# Sheet1.net
KiCad netlist of a schematic drawn in Altium Designer
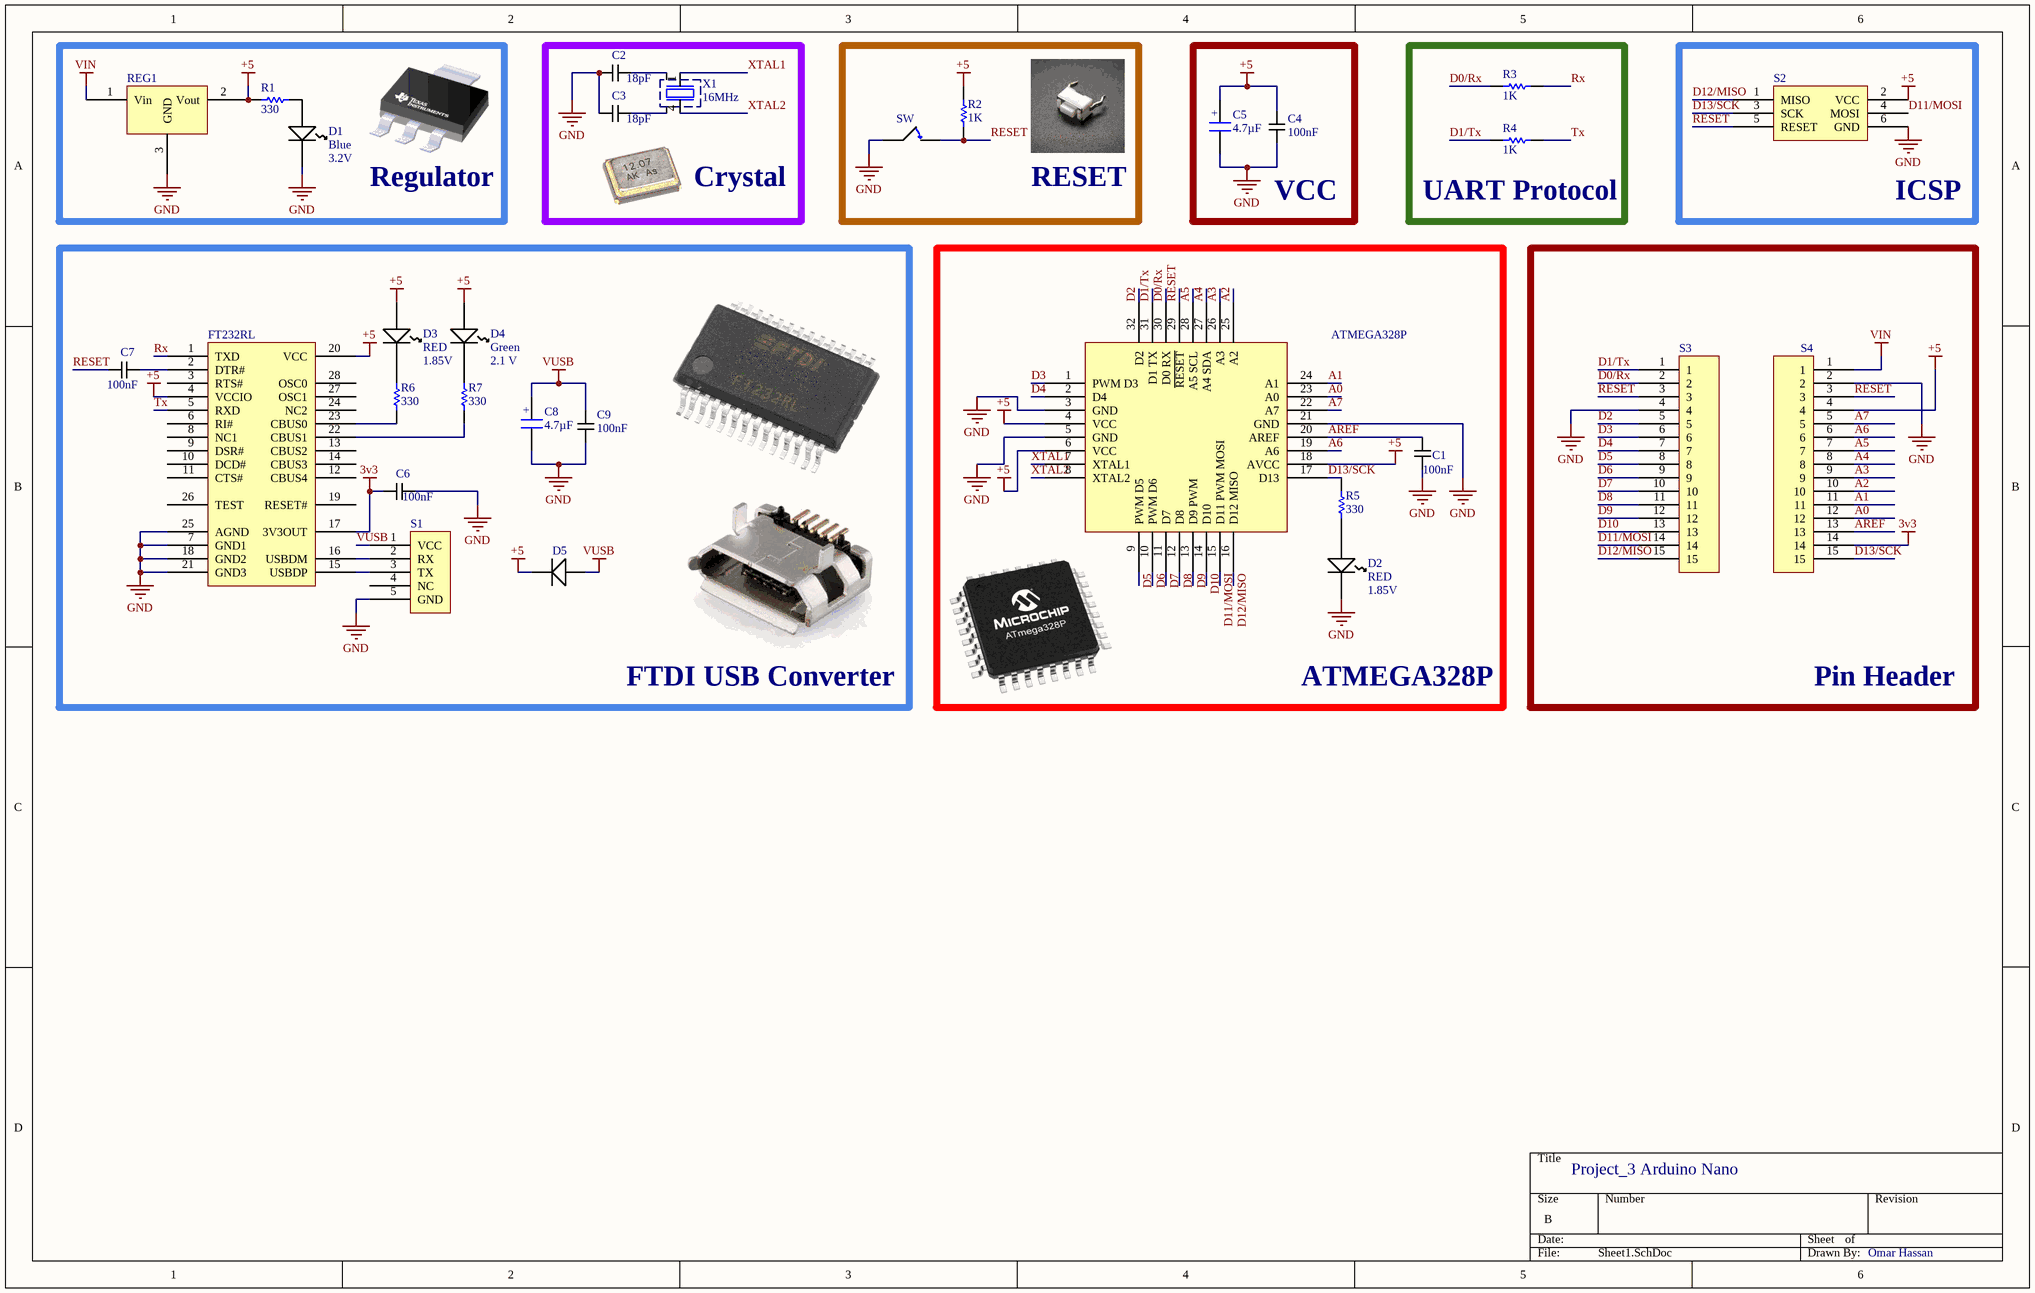
[diagram p0: Sheet1.SchDoc]

(export (version "E")
  (design (tool "Eeschema 10.0.6"))
  (components
    (comp (ref "ATMEGA328P")
      (value "ATMEGA328P-AU")
      (footprint "TQFP80P900X900X120-32N")
      (description "ATMEGA328P-AU, 8 bit AVR Microcontroller 20MHz 1 kB, 32 kB Flash, 2 kB RAM, I2C 32-Pin TQFP")
      (fields (field (name "CREATED BY") "Ritesh Kanjee"))
      (libsource (lib "Atmel Microcontrollers") (part "ATMEGA328P-AU"))
    )
    (comp (ref "C1")
      (value "100nF Ceramic Multilayer Capacitor_1")
      (footprint "CAPCP2012X09N")
      (description "AVX 0805 Standard 100nF Ceramic Multilayer Capacitor, 50 V dc X7R Dielectric ±10% SMD")
      (fields
        (field (name "MANUFACTURER") "AVX")
        (field (name "VOLTAGE") "50V")
        (field (name "CAPACITANCE") "100nF")
        (field (name "CREATOR") "Ritesh Kanjee")
      )
      (libsource (lib "RS Components - Capacitors") (part "100nF Ceramic Multilayer Capacitor_1"))
    )
    (comp (ref "C2")
      (value "C0805C180J5GACTU")
      (footprint "CAPCP2012X09N")
      (description "18pF Ceramic Multilayer Capacitor, 50 V dc C0G Dielectric ±5% SMD")
      (fields
        (field (name "MANUFACTURER") "Kemet")
        (field (name "VOLTAGE") "50V")
        (field (name "CAPACITANCE") "18pF")
        (field (name "CREATOR") "Ritesh Kanjee")
      )
      (libsource (lib "RS Components - Capacitors") (part "18pF Ceramic Multilayer Capacitor, 50 V dc C0G Dielectric ±5% SMD"))
    )
    (comp (ref "C3")
      (value "C0805C180J5GACTU")
      (footprint "CAPCP2012X09N")
      (description "18pF Ceramic Multilayer Capacitor, 50 V dc C0G Dielectric ±5% SMD")
      (fields
        (field (name "MANUFACTURER") "Kemet")
        (field (name "VOLTAGE") "50V")
        (field (name "CAPACITANCE") "18pF")
        (field (name "CREATOR") "Ritesh Kanjee")
      )
      (libsource (lib "RS Components - Capacitors") (part "18pF Ceramic Multilayer Capacitor, 50 V dc C0G Dielectric ±5% SMD"))
    )
    (comp (ref "C4")
      (value "100nF Ceramic Multilayer Capacitor_1")
      (footprint "CAPCP2012X09N")
      (description "AVX 0805 Standard 100nF Ceramic Multilayer Capacitor, 50 V dc X7R Dielectric ±10% SMD")
      (fields
        (field (name "MANUFACTURER") "AVX")
        (field (name "VOLTAGE") "50V")
        (field (name "CAPACITANCE") "100nF")
        (field (name "CREATOR") "Ritesh Kanjee")
      )
      (libsource (lib "RS Components - Capacitors") (part "100nF Ceramic Multilayer Capacitor_1"))
    )
    (comp (ref "C5")
      (value "4.7µF")
      (footprint "CASE A - 3216X18")
      (description "Capacitor,tantalum,SMT,16V,4.7uF,10%,A-case")
      (fields
        (field (name "TOLERANCE") "10%")
        (field (name "VOLTAGE") "16V")
        (field (name "PUBLISHER") "DPSS")
      )
      (libsource (lib "RS Components - Capacitors") (part "4.7µF Tant RS 496-3545"))
    )
    (comp (ref "C6")
      (value "100nF Ceramic Multilayer Capacitor_1")
      (footprint "CAPCP2012X09N")
      (description "AVX 0805 Standard 100nF Ceramic Multilayer Capacitor, 50 V dc X7R Dielectric ±10% SMD")
      (fields
        (field (name "MANUFACTURER") "AVX")
        (field (name "VOLTAGE") "50V")
        (field (name "CAPACITANCE") "100nF")
        (field (name "CREATOR") "Ritesh Kanjee")
      )
      (libsource (lib "RS Components - Capacitors") (part "100nF Ceramic Multilayer Capacitor_1"))
    )
    (comp (ref "C7")
      (value "100nF Ceramic Multilayer Capacitor_1")
      (footprint "CAPCP2012X09N")
      (description "AVX 0805 Standard 100nF Ceramic Multilayer Capacitor, 50 V dc X7R Dielectric ±10% SMD")
      (fields
        (field (name "MANUFACTURER") "AVX")
        (field (name "VOLTAGE") "50V")
        (field (name "CAPACITANCE") "100nF")
        (field (name "CREATOR") "Ritesh Kanjee")
      )
      (libsource (lib "RS Components - Capacitors") (part "100nF Ceramic Multilayer Capacitor_1"))
    )
    (comp (ref "C8")
      (value "4.7µF")
      (footprint "CASE A - 3216X18")
      (description "Capacitor,tantalum,SMT,16V,4.7uF,10%,A-case")
      (fields
        (field (name "TOLERANCE") "10%")
        (field (name "VOLTAGE") "16V")
        (field (name "PUBLISHER") "DPSS")
      )
      (libsource (lib "RS Components - Capacitors") (part "4.7µF Tant RS 496-3545"))
    )
    (comp (ref "C9")
      (value "100nF Ceramic Multilayer Capacitor_1")
      (footprint "CAPCP2012X09N")
      (description "AVX 0805 Standard 100nF Ceramic Multilayer Capacitor, 50 V dc X7R Dielectric ±10% SMD")
      (fields
        (field (name "MANUFACTURER") "AVX")
        (field (name "VOLTAGE") "50V")
        (field (name "CAPACITANCE") "100nF")
        (field (name "CREATOR") "Ritesh Kanjee")
      )
      (libsource (lib "RS Components - Capacitors") (part "100nF Ceramic Multilayer Capacitor_1"))
    )
    (comp (ref "D1")
      (value "Kingbright Blue LED, 60 mcd 120 ° 0805")
      (footprint "LED1913X12NBLUE")
      (fields
        (field (name "MANUFACTURER") "KingBright")
        (field (name "MANUFACTURER PART NO.") "KP-2012PBC-A")
        (field (name "COLOR") "Blue")
        (field (name "FORWARD VOLTAGE") "3.2V")
        (field (name "CREATOR") "Ritesh Kanjee")
      )
      (libsource (lib "KingBright LEDs") (part "Kingbright Blue LED, 60 mcd 120 ° 0805"))
    )
    (comp (ref "D2")
      (value "Kingbright Red LED, 100 mcd 120 ° 0805")
      (footprint "LED1913X12NRED")
      (fields
        (field (name "MANUFACTURER") "KingBright")
        (field (name "MANUFACTURER PART NO.") "KP-2012SRC-PRV")
        (field (name "COLOR") "RED")
        (field (name "FORWARD VOLTAGE") "1.85V")
        (field (name "CREATOR") "Ritesh Kanjee")
      )
      (libsource (lib "KingBright LEDs") (part "Kingbright Red LED, 100 mcd 120 ° 0805"))
    )
    (comp (ref "D3")
      (value "Kingbright Red LED, 100 mcd 120 ° 0805")
      (footprint "LED1913X12NRED")
      (fields
        (field (name "MANUFACTURER") "KingBright")
        (field (name "MANUFACTURER PART NO.") "KP-2012SRC-PRV")
        (field (name "COLOR") "RED")
        (field (name "FORWARD VOLTAGE") "1.85V")
        (field (name "CREATOR") "Ritesh Kanjee")
      )
      (libsource (lib "KingBright LEDs") (part "Kingbright Red LED, 100 mcd 120 ° 0805"))
    )
    (comp (ref "D4")
      (value "Kingbright Green LED, 70 mcd 120 ° 0805")
      (footprint "LED1913X12NGREEN")
      (fields
        (field (name "MANUFACTURER") "KingBright")
        (field (name "MANUFACTURER PART NO.") "KP-2012MGC")
        (field (name "COLOR") "Green")
        (field (name "FORWARD VOLTAGE") "2.1 V")
        (field (name "CREATOR") "Ritesh Kanjee")
      )
      (libsource (lib "KingBright LEDs") (part "Kingbright Green LED, 70 mcd 120 ° 0805"))
    )
    (comp (ref "D5")
      (value "Panasonic DB2J20900L Schottky Diode, 0.5A, 20V, 2.4ns, 2-Pin SMini2 F5 B")
      (footprint "DIOM1712X07N")
      (fields
        (field (name "MANUFACTURER") "Panasonic")
        (field (name "MANUFACTURER PART NO.") "DB2J20900L")
        (field (name "CREATED BY") "R Kanjee")
      )
      (libsource (lib "Panasonic Diodes") (part "Schottky Diode, 0.5A, 20V, 2.4ns, 2-Pin SMini2 F5 B"))
    )
    (comp (ref "FT232RL")
      (value "FT232RL, Universal Asynchronous Receiver & Transmitter 3MBd, 28-Pin, SSOP")
      (footprint "SOP65P780X200-28N")
      (fields
        (field (name "MANUFACTURER PART NO.") "FT232RL")
        (field (name "MANUFACTURER") "FTDI Chip")
        (field (name "CREATOR") "R Kanjee")
      )
      (libsource (lib "FTDI RS232toUSB") (part "FT232RL USB to UART, Universal Asynchronous Receiver & Transmitter 3MBd, 28-Pin, SSOP"))
    )
    (comp (ref "R1")
      (value "330")
      (description "Resistor")
      (libsource (lib "Simulation Generic Components") (part "Resistor"))
    )
    (comp (ref "R2")
      (value "1K")
      (description "Resistor")
      (libsource (lib "Simulation Generic Components") (part "Resistor"))
    )
    (comp (ref "R3")
      (value "1K")
      (description "Resistor")
      (libsource (lib "Simulation Generic Components") (part "Resistor"))
    )
    (comp (ref "R4")
      (value "1K")
      (description "Resistor")
      (libsource (lib "Simulation Generic Components") (part "Resistor"))
    )
    (comp (ref "R5")
      (value "330")
      (description "Resistor")
      (libsource (lib "Simulation Generic Components") (part "Resistor"))
    )
    (comp (ref "R6")
      (value "330")
      (description "Resistor")
      (libsource (lib "Simulation Generic Components") (part "Resistor"))
    )
    (comp (ref "R7")
      (value "330")
      (description "Resistor")
      (libsource (lib "Simulation Generic Components") (part "Resistor"))
    )
    (comp (ref "REG1")
      (value "LM1117MP-5.0/NOPB, Low Dropout Voltage Regulator, 1.5A, 5 V ±1%, 4-Pin SOT-223")
      (footprint "SOT230P700X180-4N")
      (fields (field (name "MANUFACTURER") "Texas Instruments") (field (name "CREATED BY") "R Kanjee"))
      (libsource (lib "TI Low Dropout Voltage Regulator") (part "LM1117MP-5.0"))
    )
    (comp (ref "S1")
      (value "NewMolex Right Angle SMT Female Type B Micro USB Connector, 30 V ac, 1.8A")
      (footprint "MicroUSB")
      (fields
        (field (name "MANUFACTURER") "Molex")
        (field (name "MANUFACTURER PART NO.") "105017-0001")
        (field (name "CREATOR") "R Kanjee")
      )
      (libsource (lib "Molex Connectors") (part "Micro USB Connector, 30 V ac, 1.8A"))
    )
    (comp (ref "S2")
      (value "Programming Headers Dual Row")
      (footprint "ISP HEADER")
      (fields
        (field (name "MANUFACTURER") "FCI")
        (field (name "MANUFACTURER PART NO.") "68000-236HLF")
        (field (name "CREATED BY") "R Kanjee")
      )
      (libsource (lib "PCB Headers") (part "Programming ISP, Programming Headers Dual Row"))
    )
    (comp (ref "S3")
      (value "connector;str header;single row;.1 cont centers;.095 tail;gold or gtx;36 contact")
      (footprint "Header")
      (fields
        (field (name "MANUFACTURER") "FCI")
        (field (name "MANUFACTURER PART NO.") "68000-236HLF")
        (field (name "CREATED BY") "R Kanjee")
      )
      (libsource (lib "PCB Headers") (part "Single row; PCB headers"))
    )
    (comp (ref "S4")
      (value "connector;str header;single row;.1 cont centers;.095 tail;gold or gtx;36 contact")
      (footprint "Header")
      (fields
        (field (name "MANUFACTURER") "FCI")
        (field (name "MANUFACTURER PART NO.") "68000-236HLF")
        (field (name "CREATED BY") "R Kanjee")
      )
      (libsource (lib "") (part "Single row; PCB headers_1"))
    )
    (comp (ref "SW")
      (value "Button Tactile Switch, NO 0.05 A 0.8mm")
      (footprint "Button8014X17N")
      (fields
        (field (name "MANUFACTURER") "C & K")
        (field (name "MANUFACTURER PART NO.") "B3F1000")
        (field (name "CREATOR") "R Kanjee")
      )
      (libsource (lib "Omron Tactile Switches") (part "Button Tactile Switch, NO 0.05 A 0.8mm"))
    )
    (comp (ref "X1")
      (value "16MHz")
      (footprint "Aker S5C Crystal")
      (description "Aker S5C SMT Crystal")
      (fields
        (field (name "MANUFACTURER") "Aker")
        (field (name "MANUFACTURER PART #") "C5S-16.000-12-3030-X")
        (field (name "CREATOR") "R Kanjee")
      )
      (libsource (lib "Aker Crystals") (part "Aker  C5S-16.000-12-3030-X"))
    )
  )
  (nets
    (net (code "1") (name "+5") (class "Default")
      (node (ref "ATMEGA328P") (pin "18") (pinfunction "AVCC_18") (pintype "passive"))
      (node (ref "ATMEGA328P") (pin "4") (pinfunction "VCC_4") (pintype "passive"))
      (node (ref "ATMEGA328P") (pin "6") (pinfunction "VCC_6") (pintype "passive"))
      (node (ref "C4") (pin "2") (pinfunction "2_2") (pintype "passive"))
      (node (ref "C5") (pin "1") (pinfunction "1_1") (pintype "passive"))
      (node (ref "D3") (pin "1") (pinfunction "A_1") (pintype "passive"))
      (node (ref "D4") (pin "1") (pinfunction "A_1") (pintype "passive"))
      (node (ref "D5") (pin "1") (pinfunction "1_1") (pintype "passive"))
      (node (ref "FT232RL") (pin "20") (pinfunction "VCC_20") (pintype "passive"))
      (node (ref "FT232RL") (pin "4") (pinfunction "VCCIO_4") (pintype "passive"))
      (node (ref "R1") (pin "1") (pinfunction "1_1") (pintype "passive"))
      (node (ref "R2") (pin "2") (pinfunction "2_2") (pintype "passive"))
      (node (ref "REG1") (pin "2") (pinfunction "Vout_2") (pintype "passive"))
      (node (ref "S2") (pin "2") (pinfunction "VCC_2") (pintype "passive"))
      (node (ref "S4") (pin "4") (pinfunction "4_4") (pintype "passive"))
    )
    (net (code "2") (name "/A0") (class "Default")
      (node (ref "ATMEGA328P") (pin "23") (pinfunction "A0_23") (pintype "passive"))
      (node (ref "S4") (pin "12") (pinfunction "12_12") (pintype "passive"))
    )
    (net (code "3") (name "/A1") (class "Default")
      (node (ref "ATMEGA328P") (pin "24") (pinfunction "A1_24") (pintype "passive"))
      (node (ref "S4") (pin "11") (pinfunction "11_11") (pintype "passive"))
    )
    (net (code "4") (name "/A2") (class "Default")
      (node (ref "ATMEGA328P") (pin "25") (pinfunction "A2_25") (pintype "passive"))
      (node (ref "S4") (pin "10") (pinfunction "10_10") (pintype "passive"))
    )
    (net (code "5") (name "/A3") (class "Default")
      (node (ref "ATMEGA328P") (pin "26") (pinfunction "A3_26") (pintype "passive"))
      (node (ref "S4") (pin "9") (pinfunction "9_9") (pintype "passive"))
    )
    (net (code "6") (name "/A4") (class "Default")
      (node (ref "ATMEGA328P") (pin "27") (pinfunction "A4_SDA_27") (pintype "passive"))
      (node (ref "S4") (pin "8") (pinfunction "8_8") (pintype "passive"))
    )
    (net (code "7") (name "/A5") (class "Default")
      (node (ref "ATMEGA328P") (pin "28") (pinfunction "A5_SCL_28") (pintype "passive"))
      (node (ref "S4") (pin "7") (pinfunction "7_7") (pintype "passive"))
    )
    (net (code "8") (name "/A6") (class "Default")
      (node (ref "ATMEGA328P") (pin "19") (pinfunction "A6_19") (pintype "passive"))
      (node (ref "S4") (pin "6") (pinfunction "6_6") (pintype "passive"))
    )
    (net (code "9") (name "/A7") (class "Default")
      (node (ref "ATMEGA328P") (pin "22") (pinfunction "A7_22") (pintype "passive"))
      (node (ref "S4") (pin "5") (pinfunction "5_5") (pintype "passive"))
    )
    (net (code "10") (name "/AREF") (class "Default")
      (node (ref "ATMEGA328P") (pin "20") (pinfunction "AREF_20") (pintype "passive"))
      (node (ref "C1") (pin "2") (pinfunction "2_2") (pintype "passive"))
      (node (ref "S4") (pin "13") (pinfunction "13_13") (pintype "passive"))
    )
    (net (code "11") (name "/D0{slash}Rx") (class "Default")
      (node (ref "ATMEGA328P") (pin "30") (pinfunction "D0_RX_30") (pintype "passive"))
      (node (ref "R3") (pin "1") (pinfunction "1_1") (pintype "passive"))
      (node (ref "S3") (pin "2") (pinfunction "2_2") (pintype "passive"))
    )
    (net (code "12") (name "/D1{slash}Tx") (class "Default")
      (node (ref "ATMEGA328P") (pin "31") (pinfunction "D1_TX_31") (pintype "passive"))
      (node (ref "R4") (pin "1") (pinfunction "1_1") (pintype "passive"))
      (node (ref "S3") (pin "1") (pinfunction "1_1") (pintype "passive"))
    )
    (net (code "13") (name "/D2") (class "Default")
      (node (ref "ATMEGA328P") (pin "32") (pinfunction "D2_32") (pintype "passive"))
      (node (ref "S3") (pin "5") (pinfunction "5_5") (pintype "passive"))
    )
    (net (code "14") (name "/D3") (class "Default")
      (node (ref "ATMEGA328P") (pin "1") (pinfunction "PWM_D3_1") (pintype "passive"))
      (node (ref "S3") (pin "6") (pinfunction "6_6") (pintype "passive"))
    )
    (net (code "15") (name "/D4") (class "Default")
      (node (ref "ATMEGA328P") (pin "2") (pinfunction "D4_2") (pintype "passive"))
      (node (ref "S3") (pin "7") (pinfunction "7_7") (pintype "passive"))
    )
    (net (code "16") (name "/D5") (class "Default")
      (node (ref "ATMEGA328P") (pin "9") (pinfunction "PWM_D5_9") (pintype "passive"))
      (node (ref "S3") (pin "8") (pinfunction "8_8") (pintype "passive"))
    )
    (net (code "17") (name "/D6") (class "Default")
      (node (ref "ATMEGA328P") (pin "10") (pinfunction "PWM_D6_10") (pintype "passive"))
      (node (ref "S3") (pin "9") (pinfunction "9_9") (pintype "passive"))
    )
    (net (code "18") (name "/D7") (class "Default")
      (node (ref "ATMEGA328P") (pin "11") (pinfunction "D7_11") (pintype "passive"))
      (node (ref "S3") (pin "10") (pinfunction "10_10") (pintype "passive"))
    )
    (net (code "19") (name "/D8") (class "Default")
      (node (ref "ATMEGA328P") (pin "12") (pinfunction "D8_12") (pintype "passive"))
      (node (ref "S3") (pin "11") (pinfunction "11_11") (pintype "passive"))
    )
    (net (code "20") (name "/D9") (class "Default")
      (node (ref "ATMEGA328P") (pin "13") (pinfunction "D9_PWM_13") (pintype "passive"))
      (node (ref "S3") (pin "12") (pinfunction "12_12") (pintype "passive"))
    )
    (net (code "21") (name "/D10") (class "Default")
      (node (ref "ATMEGA328P") (pin "14") (pinfunction "D10_14") (pintype "passive"))
      (node (ref "S3") (pin "13") (pinfunction "13_13") (pintype "passive"))
    )
    (net (code "22") (name "/D11{slash}MOSI") (class "Default")
      (node (ref "ATMEGA328P") (pin "15") (pinfunction "D11_PWM_MOSI_15") (pintype "passive"))
      (node (ref "S2") (pin "4") (pinfunction "MOSI_4") (pintype "passive"))
      (node (ref "S3") (pin "14") (pinfunction "14_14") (pintype "passive"))
    )
    (net (code "23") (name "/D12{slash}MISO") (class "Default")
      (node (ref "ATMEGA328P") (pin "16") (pinfunction "D12_MISO_16") (pintype "passive"))
      (node (ref "S2") (pin "1") (pinfunction "MISO_1") (pintype "passive"))
      (node (ref "S3") (pin "15") (pinfunction "15_15") (pintype "passive"))
    )
    (net (code "24") (name "/D13{slash}SCK") (class "Default")
      (node (ref "ATMEGA328P") (pin "17") (pinfunction "D13_17") (pintype "passive"))
      (node (ref "R5") (pin "2") (pinfunction "2_2") (pintype "passive"))
      (node (ref "S2") (pin "3") (pinfunction "SCK_3") (pintype "passive"))
      (node (ref "S4") (pin "15") (pinfunction "15_15") (pintype "passive"))
    )
    (net (code "25") (name "/RESET") (class "Default")
      (node (ref "ATMEGA328P") (pin "29") (pinfunction "~{RESET}_29") (pintype "passive"))
      (node (ref "C7") (pin "1") (pinfunction "1_1") (pintype "passive"))
      (node (ref "R2") (pin "1") (pinfunction "1_1") (pintype "passive"))
      (node (ref "S2") (pin "5") (pinfunction "RESET_5") (pintype "passive"))
      (node (ref "S3") (pin "3") (pinfunction "3_3") (pintype "passive"))
      (node (ref "S4") (pin "3") (pinfunction "3_3") (pintype "passive"))
      (node (ref "SW") (pin "1") (pinfunction "1_1") (pintype "passive"))
    )
    (net (code "26") (name "/Rx") (class "Default")
      (node (ref "FT232RL") (pin "1") (pinfunction "TXD_1") (pintype "passive"))
      (node (ref "R3") (pin "2") (pinfunction "2_2") (pintype "passive"))
    )
    (net (code "27") (name "/Tx") (class "Default")
      (node (ref "FT232RL") (pin "5") (pinfunction "RXD_5") (pintype "passive"))
      (node (ref "R4") (pin "2") (pinfunction "2_2") (pintype "passive"))
    )
    (net (code "28") (name "/XTAL1") (class "Default")
      (node (ref "ATMEGA328P") (pin "7") (pinfunction "XTAL1_7") (pintype "passive"))
      (node (ref "X1") (pin "1") (pinfunction "1_1") (pintype "passive"))
    )
    (net (code "29") (name "/XTAL2") (class "Default")
      (node (ref "ATMEGA328P") (pin "8") (pinfunction "XTAL2_8") (pintype "passive"))
      (node (ref "X1") (pin "4") (pinfunction "4_4") (pintype "passive"))
    )
    (net (code "30") (name "3v3") (class "Default")
      (node (ref "C6") (pin "1") (pinfunction "1_1") (pintype "passive"))
      (node (ref "FT232RL") (pin "17") (pinfunction "3V3OUT_17") (pintype "passive"))
      (node (ref "S4") (pin "14") (pinfunction "14_14") (pintype "passive"))
    )
    (net (code "31") (name "GND") (class "Default")
      (node (ref "ATMEGA328P") (pin "21") (pinfunction "GND_21") (pintype "passive"))
      (node (ref "ATMEGA328P") (pin "3") (pinfunction "GND_3") (pintype "passive"))
      (node (ref "ATMEGA328P") (pin "5") (pinfunction "GND_5") (pintype "passive"))
      (node (ref "C1") (pin "1") (pinfunction "1_1") (pintype "passive"))
      (node (ref "C2") (pin "1") (pinfunction "1_1") (pintype "passive"))
      (node (ref "C3") (pin "1") (pinfunction "1_1") (pintype "passive"))
      (node (ref "C4") (pin "1") (pinfunction "1_1") (pintype "passive"))
      (node (ref "C5") (pin "2") (pinfunction "2_2") (pintype "passive"))
      (node (ref "C6") (pin "2") (pinfunction "2_2") (pintype "passive"))
      (node (ref "C8") (pin "2") (pinfunction "2_2") (pintype "passive"))
      (node (ref "C9") (pin "1") (pinfunction "1_1") (pintype "passive"))
      (node (ref "D1") (pin "2") (pinfunction "K_2") (pintype "passive"))
      (node (ref "D2") (pin "2") (pinfunction "K_2") (pintype "passive"))
      (node (ref "FT232RL") (pin "18") (pinfunction "GND2_18") (pintype "passive"))
      (node (ref "FT232RL") (pin "21") (pinfunction "GND3_21") (pintype "passive"))
      (node (ref "FT232RL") (pin "25") (pinfunction "AGND_25") (pintype "passive"))
      (node (ref "FT232RL") (pin "7") (pinfunction "GND1_7") (pintype "passive"))
      (node (ref "REG1") (pin "3") (pinfunction "GND_3") (pintype "passive"))
      (node (ref "S1") (pin "5") (pinfunction "GND_5") (pintype "passive"))
      (node (ref "S2") (pin "6") (pinfunction "GND_6") (pintype "passive"))
      (node (ref "S3") (pin "4") (pinfunction "4_4") (pintype "passive"))
      (node (ref "S4") (pin "2") (pinfunction "2_2") (pintype "passive"))
      (node (ref "SW") (pin "1") (pinfunction "1_1") (pintype "passive"))
    )
    (net (code "32") (name "Net-(C2-Pad2)") (class "Default")
      (node (ref "C2") (pin "2") (pinfunction "2_2") (pintype "passive"))
      (node (ref "X1") (pin "3") (pinfunction "Gnd_3") (pintype "power_in"))
    )
    (net (code "33") (name "Net-(C3-Pad2)") (class "Default")
      (node (ref "C3") (pin "2") (pinfunction "2_2") (pintype "passive"))
      (node (ref "X1") (pin "2") (pinfunction "Gnd_2") (pintype "power_in"))
    )
    (net (code "34") (name "Net-(D1-A)") (class "Default")
      (node (ref "D1") (pin "1") (pinfunction "A_1") (pintype "passive"))
      (node (ref "R1") (pin "2") (pinfunction "2_2") (pintype "passive"))
    )
    (net (code "35") (name "Net-(D2-A)") (class "Default")
      (node (ref "D2") (pin "1") (pinfunction "A_1") (pintype "passive"))
      (node (ref "R5") (pin "1") (pinfunction "1_1") (pintype "passive"))
    )
    (net (code "36") (name "Net-(D3-K)") (class "Default")
      (node (ref "D3") (pin "2") (pinfunction "K_2") (pintype "passive"))
      (node (ref "R6") (pin "2") (pinfunction "2_2") (pintype "passive"))
    )
    (net (code "37") (name "Net-(D4-K)") (class "Default")
      (node (ref "D4") (pin "2") (pinfunction "K_2") (pintype "passive"))
      (node (ref "R7") (pin "2") (pinfunction "2_2") (pintype "passive"))
    )
    (net (code "38") (name "Net-(FT232RL-CBUS0)") (class "Default")
      (node (ref "FT232RL") (pin "23") (pinfunction "CBUS0_23") (pintype "passive"))
      (node (ref "R6") (pin "1") (pinfunction "1_1") (pintype "passive"))
    )
    (net (code "39") (name "Net-(FT232RL-CBUS1)") (class "Default")
      (node (ref "FT232RL") (pin "22") (pinfunction "CBUS1_22") (pintype "passive"))
      (node (ref "R7") (pin "1") (pinfunction "1_1") (pintype "passive"))
    )
    (net (code "40") (name "Net-(FT232RL-DTR#)") (class "Default")
      (node (ref "C7") (pin "2") (pinfunction "2_2") (pintype "passive"))
      (node (ref "FT232RL") (pin "2") (pinfunction "DTR#_2") (pintype "passive"))
    )
    (net (code "41") (name "Net-(FT232RL-USBDM)") (class "Default")
      (node (ref "FT232RL") (pin "16") (pinfunction "USBDM_16") (pintype "passive"))
      (node (ref "S1") (pin "2") (pinfunction "RX_2") (pintype "passive"))
    )
    (net (code "42") (name "Net-(FT232RL-USBDP)") (class "Default")
      (node (ref "FT232RL") (pin "15") (pinfunction "USBDP_15") (pintype "passive"))
      (node (ref "S1") (pin "3") (pinfunction "TX_3") (pintype "passive"))
    )
    (net (code "43") (name "VIN") (class "Default")
      (node (ref "REG1") (pin "1") (pinfunction "Vin_1") (pintype "passive"))
      (node (ref "S4") (pin "1") (pinfunction "1_1") (pintype "passive"))
    )
    (net (code "44") (name "VUSB") (class "Default")
      (node (ref "C8") (pin "1") (pinfunction "1_1") (pintype "passive"))
      (node (ref "C9") (pin "2") (pinfunction "2_2") (pintype "passive"))
      (node (ref "D5") (pin "2") (pinfunction "2_2") (pintype "passive"))
      (node (ref "S1") (pin "1") (pinfunction "VCC_1") (pintype "passive"))
    )
    (net (code "45") (name "unconnected-(FT232RL-CBUS2-Pad13)") (class "Default")
      (node (ref "FT232RL") (pin "13") (pinfunction "CBUS2_13") (pintype "passive"))
    )
    (net (code "46") (name "unconnected-(FT232RL-CBUS3-Pad14)") (class "Default")
      (node (ref "FT232RL") (pin "14") (pinfunction "CBUS3_14") (pintype "passive"))
    )
    (net (code "47") (name "unconnected-(FT232RL-CBUS4-Pad12)") (class "Default")
      (node (ref "FT232RL") (pin "12") (pinfunction "CBUS4_12") (pintype "passive"))
    )
    (net (code "48") (name "unconnected-(FT232RL-CTS#-Pad11)") (class "Default")
      (node (ref "FT232RL") (pin "11") (pinfunction "CTS#_11") (pintype "passive"))
    )
    (net (code "49") (name "unconnected-(FT232RL-DCD#-Pad10)") (class "Default")
      (node (ref "FT232RL") (pin "10") (pinfunction "DCD#_10") (pintype "passive"))
    )
    (net (code "50") (name "unconnected-(FT232RL-DSR#-Pad9)") (class "Default")
      (node (ref "FT232RL") (pin "9") (pinfunction "DSR#_9") (pintype "passive"))
    )
    (net (code "51") (name "unconnected-(FT232RL-NC1-Pad8)") (class "Default")
      (node (ref "FT232RL") (pin "8") (pinfunction "NC1_8") (pintype "passive"))
    )
    (net (code "52") (name "unconnected-(FT232RL-NC2-Pad24)") (class "Default")
      (node (ref "FT232RL") (pin "24") (pinfunction "NC2_24") (pintype "passive"))
    )
    (net (code "53") (name "unconnected-(FT232RL-OSC0-Pad28)") (class "Default")
      (node (ref "FT232RL") (pin "28") (pinfunction "OSC0_28") (pintype "passive"))
    )
    (net (code "54") (name "unconnected-(FT232RL-OSC1-Pad27)") (class "Default")
      (node (ref "FT232RL") (pin "27") (pinfunction "OSC1_27") (pintype "passive"))
    )
    (net (code "55") (name "unconnected-(FT232RL-RESET#-Pad19)") (class "Default")
      (node (ref "FT232RL") (pin "19") (pinfunction "RESET#_19") (pintype "passive"))
    )
    (net (code "56") (name "unconnected-(FT232RL-RI#-Pad6)") (class "Default")
      (node (ref "FT232RL") (pin "6") (pinfunction "RI#_6") (pintype "passive"))
    )
    (net (code "57") (name "unconnected-(FT232RL-RTS#-Pad3)") (class "Default")
      (node (ref "FT232RL") (pin "3") (pinfunction "RTS#_3") (pintype "passive"))
    )
    (net (code "58") (name "unconnected-(FT232RL-TEST-Pad26)") (class "Default")
      (node (ref "FT232RL") (pin "26") (pinfunction "TEST_26") (pintype "passive"))
    )
    (net (code "59") (name "unconnected-(S1-NC-Pad4)") (class "Default")
      (node (ref "S1") (pin "4") (pinfunction "NC_4") (pintype "passive"))
    )
  )
)
